# brick_serial_ble.net
KiCad netlist of a schematic drawn in EAGLE
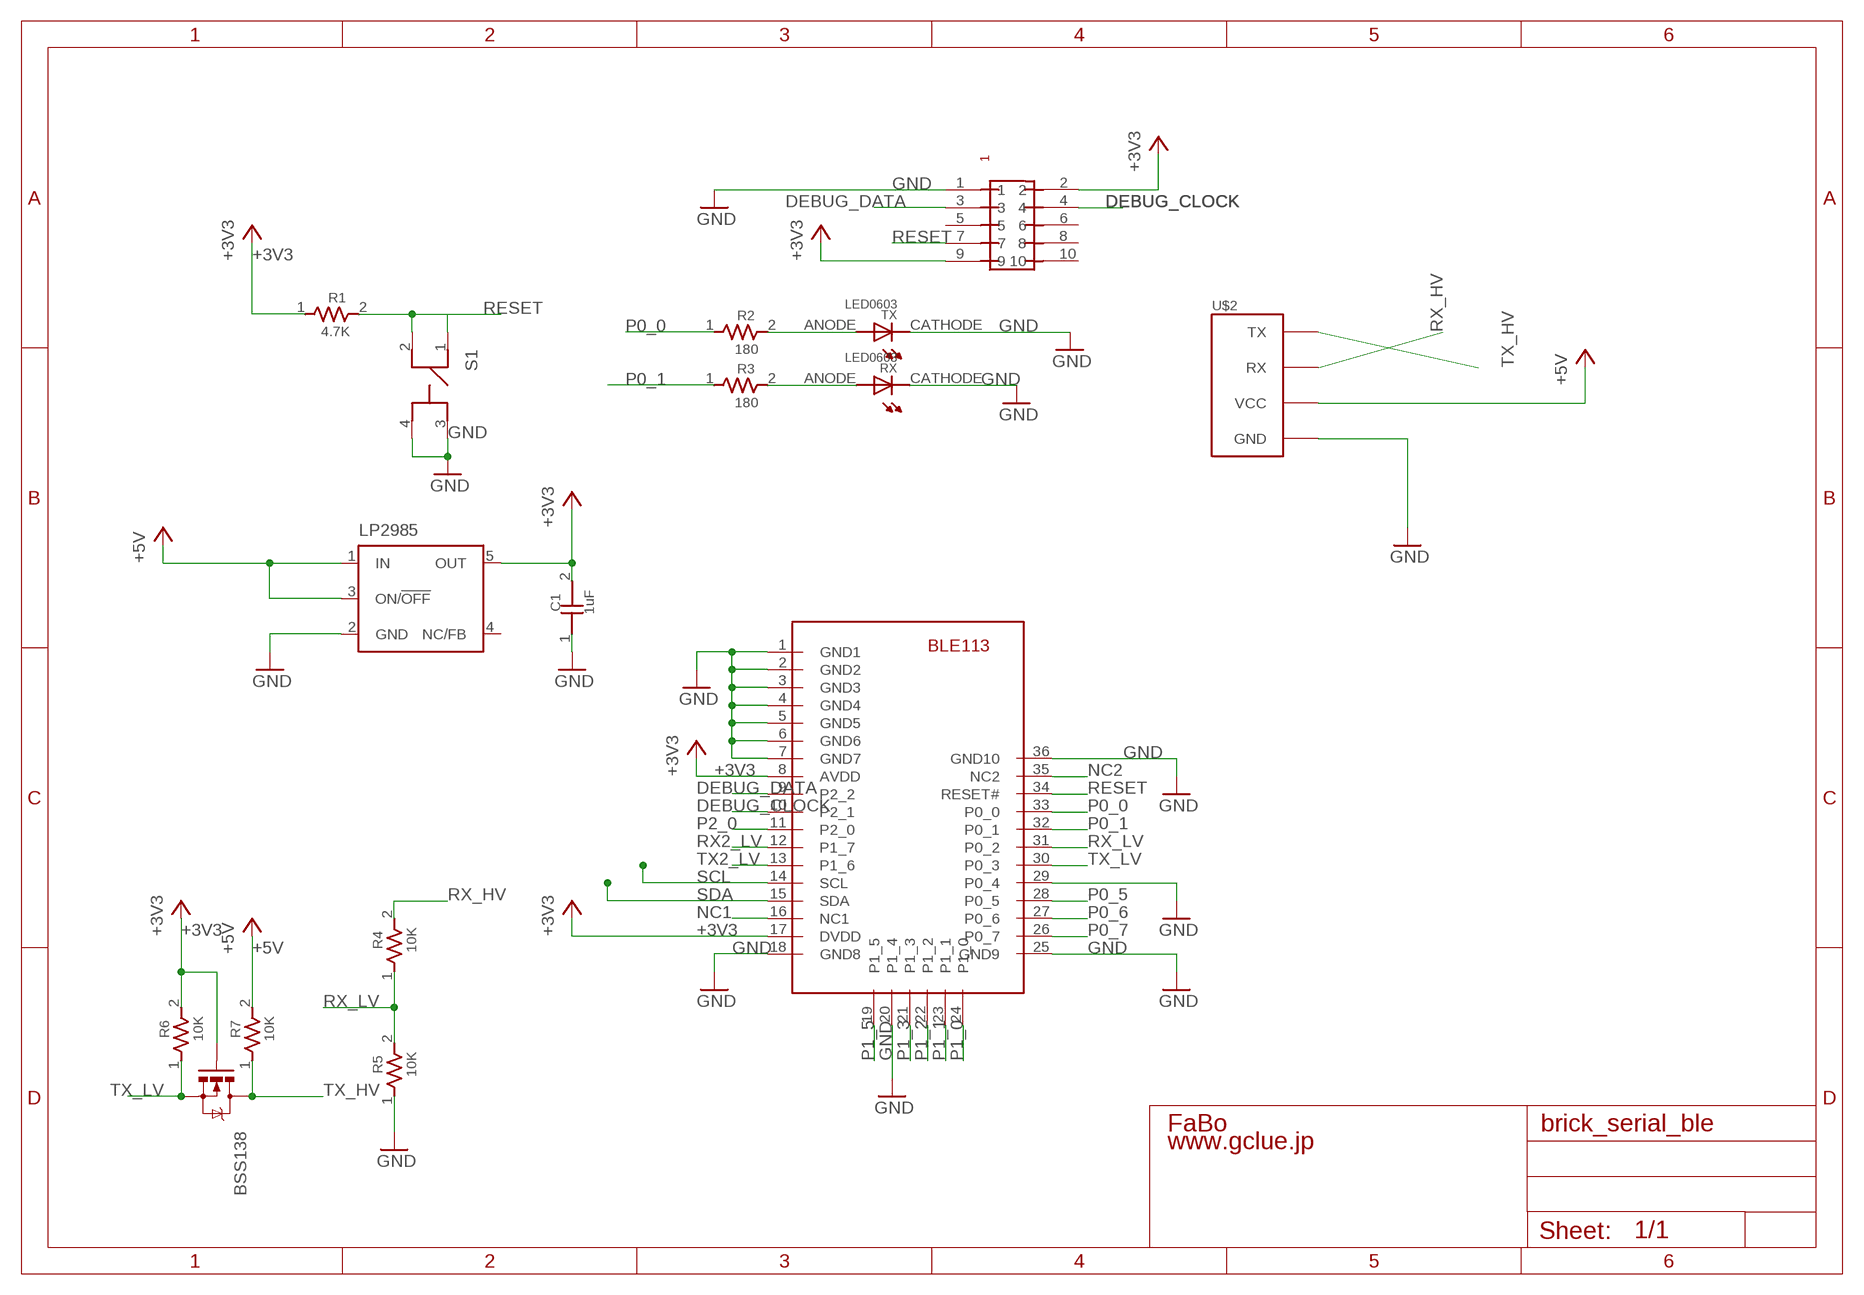
[diagram p0: schematic, sheet 1]

(export (version "E")
  (design (tool "Eeschema 10.0.6"))
  (components
    (comp (ref "BSS138")
      (value "MOSFET-NCHANNELSMD")
      (footprint "eagle-import:SOT23-3")
      (libsource (lib "eagle-import") (part "MOSFET-NCHANNELSMD"))
    )
    (comp (ref "C1")
      (value "1uF")
      (footprint "eagle-import:0603")
      (libsource (lib "eagle-import") (part "CAPACITOR0603"))
    )
    (comp (ref "LP2985")
      (value "LP2985-XXDBVR33")
      (footprint "eagle-import:SOT23-DBV")
      (libsource (lib "eagle-import") (part "LP2985-XXDBVR33"))
    )
    (comp (ref "R1")
      (value "4.7K")
      (footprint "eagle-import:0603")
      (libsource (lib "eagle-import") (part "RESISTOR0603"))
    )
    (comp (ref "R2")
      (value "180")
      (footprint "eagle-import:0603")
      (libsource (lib "eagle-import") (part "RESISTOR0603"))
    )
    (comp (ref "R3")
      (value "180")
      (footprint "eagle-import:0603")
      (libsource (lib "eagle-import") (part "RESISTOR0603"))
    )
    (comp (ref "R4")
      (value "10K")
      (footprint "eagle-import:0603")
      (libsource (lib "eagle-import") (part "RESISTOR0603"))
    )
    (comp (ref "R5")
      (value "10K")
      (footprint "eagle-import:0603")
      (libsource (lib "eagle-import") (part "RESISTOR0603"))
    )
    (comp (ref "R6")
      (value "10K")
      (footprint "eagle-import:0603")
      (libsource (lib "eagle-import") (part "RESISTOR0603"))
    )
    (comp (ref "R7")
      (value "10K")
      (footprint "eagle-import:0603")
      (libsource (lib "eagle-import") (part "RESISTOR0603"))
    )
    (comp (ref "RX")
      (value "LED0603")
      (footprint "eagle-import:0603")
      (libsource (lib "eagle-import") (part "LED0603"))
    )
    (comp (ref "S1")
      (value "SWITCH-LS6J2M-T")
      (footprint "eagle-import:SWITCH-LS6J2M-T")
      (libsource (lib "eagle-import") (part "SWITCH-LS6J2M-T"))
    )
    (comp (ref "TX")
      (value "LED0603")
      (footprint "eagle-import:0603")
      (libsource (lib "eagle-import") (part "LED0603"))
    )
    (comp (ref "U$1")
      (value "PIN-HEADER-SMT(1.27MM)2X5")
      (footprint "eagle-import:PIN-HEADER-SMT(1.27MM)2X5")
      (libsource (lib "eagle-import") (part "PIN-HEADER-SMT(1.27MM)2X5"))
    )
    (comp (ref "U$2")
      (value "BRICK_SERIAL")
      (footprint "eagle-import:BRICK_SERIAL")
      (libsource (lib "eagle-import") (part "BRICK_SERIAL"))
    )
    (comp (ref "U$6")
      (value "BLUEGIGA-BLE113")
      (footprint "eagle-import:BLUEGIGA-BLE113")
      (libsource (lib "eagle-import") (part "BLUEGIGA-BLE113"))
    )
  )
  (nets
    (net (code "1") (name "+3V3") (class "Default")
      (node (ref "BSS138") (pin "1") (pinfunction "G_1") (pintype "passive"))
      (node (ref "C1") (pin "2") (pinfunction "2_2") (pintype "passive"))
      (node (ref "LP2985") (pin "5") (pinfunction "OUT_5") (pintype "passive"))
      (node (ref "R1") (pin "1") (pinfunction "1_1") (pintype "passive"))
      (node (ref "R6") (pin "2") (pinfunction "2_2") (pintype "passive"))
      (node (ref "U$1") (pin "2") (pinfunction "2_2") (pintype "bidirectional"))
      (node (ref "U$1") (pin "9") (pinfunction "9_9") (pintype "bidirectional"))
      (node (ref "U$6") (pin "17") (pinfunction "DVDD_17") (pintype "bidirectional"))
      (node (ref "U$6") (pin "8") (pinfunction "AVDD_8") (pintype "bidirectional"))
    )
    (net (code "2") (name "+5V") (class "Default")
      (node (ref "LP2985") (pin "1") (pinfunction "IN_1") (pintype "input"))
      (node (ref "LP2985") (pin "3") (pinfunction "ON/~{OFF}_3") (pintype "input"))
      (node (ref "R7") (pin "2") (pinfunction "2_2") (pintype "passive"))
      (node (ref "U$2") (pin "VCC") (pinfunction "VCC_VCC") (pintype "bidirectional"))
    )
    (net (code "3") (name "/DEBUG_CLOCK") (class "Default")
      (node (ref "U$1") (pin "4") (pinfunction "4_4") (pintype "bidirectional"))
      (node (ref "U$6") (pin "10") (pinfunction "P2_1_10") (pintype "bidirectional"))
    )
    (net (code "4") (name "/DEBUG_DATA") (class "Default")
      (node (ref "U$1") (pin "3") (pinfunction "3_3") (pintype "bidirectional"))
      (node (ref "U$6") (pin "9") (pinfunction "P2_2_9") (pintype "bidirectional"))
    )
    (net (code "5") (name "/NC1") (class "Default")
      (node (ref "U$6") (pin "16") (pinfunction "NC1_16") (pintype "bidirectional"))
    )
    (net (code "6") (name "/NC2") (class "Default")
      (node (ref "U$6") (pin "35") (pinfunction "NC2_35") (pintype "bidirectional"))
    )
    (net (code "7") (name "/P0_0") (class "Default")
      (node (ref "R2") (pin "1") (pinfunction "1_1") (pintype "passive"))
      (node (ref "U$6") (pin "33") (pinfunction "P0_0_33") (pintype "bidirectional"))
    )
    (net (code "8") (name "/P0_1") (class "Default")
      (node (ref "R3") (pin "1") (pinfunction "1_1") (pintype "passive"))
      (node (ref "U$6") (pin "32") (pinfunction "P0_1_32") (pintype "bidirectional"))
    )
    (net (code "9") (name "/P0_5") (class "Default")
      (node (ref "U$6") (pin "28") (pinfunction "P0_5_28") (pintype "bidirectional"))
    )
    (net (code "10") (name "/P0_6") (class "Default")
      (node (ref "U$6") (pin "27") (pinfunction "P0_6_27") (pintype "bidirectional"))
    )
    (net (code "11") (name "/P0_7") (class "Default")
      (node (ref "U$6") (pin "26") (pinfunction "P0_7_26") (pintype "bidirectional"))
    )
    (net (code "12") (name "/P1_0") (class "Default")
      (node (ref "U$6") (pin "24") (pinfunction "P1_0_24") (pintype "bidirectional"))
    )
    (net (code "13") (name "/P1_1") (class "Default")
      (node (ref "U$6") (pin "23") (pinfunction "P1_1_23") (pintype "bidirectional"))
    )
    (net (code "14") (name "/P1_2") (class "Default")
      (node (ref "U$6") (pin "22") (pinfunction "P1_2_22") (pintype "bidirectional"))
    )
    (net (code "15") (name "/P1_3") (class "Default")
      (node (ref "U$6") (pin "21") (pinfunction "P1_3_21") (pintype "bidirectional"))
    )
    (net (code "16") (name "/P1_5") (class "Default")
      (node (ref "U$6") (pin "19") (pinfunction "P1_5_19") (pintype "bidirectional"))
    )
    (net (code "17") (name "/P2_0") (class "Default")
      (node (ref "U$6") (pin "11") (pinfunction "P2_0_11") (pintype "bidirectional"))
    )
    (net (code "18") (name "/RESET") (class "Default")
      (node (ref "R1") (pin "2") (pinfunction "2_2") (pintype "passive"))
      (node (ref "S1") (pin "1") (pinfunction "1_1") (pintype "bidirectional"))
      (node (ref "S1") (pin "2") (pinfunction "2_2") (pintype "bidirectional"))
      (node (ref "U$1") (pin "7") (pinfunction "7_7") (pintype "bidirectional"))
      (node (ref "U$6") (pin "34") (pinfunction "RESET#_34") (pintype "bidirectional"))
    )
    (net (code "19") (name "/RX2_LV") (class "Default")
      (node (ref "U$6") (pin "12") (pinfunction "P1_7_12") (pintype "bidirectional"))
    )
    (net (code "20") (name "/RX_HV") (class "Default")
      (node (ref "R4") (pin "2") (pinfunction "2_2") (pintype "passive"))
      (node (ref "U$2") (pin "RX") (pinfunction "RX_RX") (pintype "bidirectional"))
    )
    (net (code "21") (name "/RX_LV") (class "Default")
      (node (ref "R4") (pin "1") (pinfunction "1_1") (pintype "passive"))
      (node (ref "R5") (pin "2") (pinfunction "2_2") (pintype "passive"))
      (node (ref "U$6") (pin "31") (pinfunction "P0_2_31") (pintype "bidirectional"))
    )
    (net (code "22") (name "/SCL") (class "Default")
      (node (ref "U$6") (pin "14") (pinfunction "SCL_14") (pintype "bidirectional"))
    )
    (net (code "23") (name "/SDA") (class "Default")
      (node (ref "U$6") (pin "15") (pinfunction "SDA_15") (pintype "bidirectional"))
    )
    (net (code "24") (name "/TX2_LV") (class "Default")
      (node (ref "U$6") (pin "13") (pinfunction "P1_6_13") (pintype "bidirectional"))
    )
    (net (code "25") (name "/TX_HV") (class "Default")
      (node (ref "BSS138") (pin "3") (pinfunction "D_3") (pintype "passive"))
      (node (ref "R7") (pin "1") (pinfunction "1_1") (pintype "passive"))
      (node (ref "U$2") (pin "TX") (pinfunction "TX_TX") (pintype "bidirectional"))
    )
    (net (code "26") (name "/TX_LV") (class "Default")
      (node (ref "BSS138") (pin "2") (pinfunction "S_2") (pintype "passive"))
      (node (ref "R6") (pin "1") (pinfunction "1_1") (pintype "passive"))
      (node (ref "U$6") (pin "30") (pinfunction "P0_3_30") (pintype "bidirectional"))
    )
    (net (code "27") (name "GND") (class "Default")
      (node (ref "C1") (pin "1") (pinfunction "1_1") (pintype "passive"))
      (node (ref "LP2985") (pin "2") (pinfunction "GND_2") (pintype "power_in"))
      (node (ref "R5") (pin "1") (pinfunction "1_1") (pintype "passive"))
      (node (ref "RX") (pin "CATHODE") (pinfunction "CATHODE_CATHODE") (pintype "passive"))
      (node (ref "S1") (pin "3") (pinfunction "3_3") (pintype "bidirectional"))
      (node (ref "S1") (pin "4") (pinfunction "4_4") (pintype "bidirectional"))
      (node (ref "TX") (pin "CATHODE") (pinfunction "CATHODE_CATHODE") (pintype "passive"))
      (node (ref "U$1") (pin "1") (pinfunction "1_1") (pintype "bidirectional"))
      (node (ref "U$2") (pin "GND") (pinfunction "GND_GND") (pintype "bidirectional"))
      (node (ref "U$6") (pin "1") (pinfunction "GND1_1") (pintype "bidirectional"))
      (node (ref "U$6") (pin "18") (pinfunction "GND8_18") (pintype "bidirectional"))
      (node (ref "U$6") (pin "2") (pinfunction "GND2_2") (pintype "bidirectional"))
      (node (ref "U$6") (pin "20") (pinfunction "P1_4_20") (pintype "bidirectional"))
      (node (ref "U$6") (pin "25") (pinfunction "GND9_25") (pintype "bidirectional"))
      (node (ref "U$6") (pin "29") (pinfunction "P0_4_29") (pintype "bidirectional"))
      (node (ref "U$6") (pin "3") (pinfunction "GND3_3") (pintype "bidirectional"))
      (node (ref "U$6") (pin "36") (pinfunction "GND10_36") (pintype "bidirectional"))
      (node (ref "U$6") (pin "4") (pinfunction "GND4_4") (pintype "bidirectional"))
      (node (ref "U$6") (pin "5") (pinfunction "GND5_5") (pintype "bidirectional"))
      (node (ref "U$6") (pin "6") (pinfunction "GND6_6") (pintype "bidirectional"))
      (node (ref "U$6") (pin "7") (pinfunction "GND7_7") (pintype "bidirectional"))
    )
    (net (code "28") (name "Net-(R2-Pad2)") (class "Default")
      (node (ref "R2") (pin "2") (pinfunction "2_2") (pintype "passive"))
      (node (ref "TX") (pin "ANODE") (pinfunction "ANODE_ANODE") (pintype "passive"))
    )
    (net (code "29") (name "Net-(R3-Pad2)") (class "Default")
      (node (ref "R3") (pin "2") (pinfunction "2_2") (pintype "passive"))
      (node (ref "RX") (pin "ANODE") (pinfunction "ANODE_ANODE") (pintype "passive"))
    )
    (net (code "30") (name "unconnected-(LP2985-NC{slash}FB-Pad4)") (class "Default")
      (node (ref "LP2985") (pin "4") (pinfunction "NC/FB_4") (pintype "passive"))
    )
    (net (code "31") (name "unconnected-(U$1-Pad5)") (class "Default")
      (node (ref "U$1") (pin "5") (pinfunction "5_5") (pintype "bidirectional"))
    )
    (net (code "32") (name "unconnected-(U$1-Pad6)") (class "Default")
      (node (ref "U$1") (pin "6") (pinfunction "6_6") (pintype "bidirectional"))
    )
    (net (code "33") (name "unconnected-(U$1-Pad8)") (class "Default")
      (node (ref "U$1") (pin "8") (pinfunction "8_8") (pintype "bidirectional"))
    )
    (net (code "34") (name "unconnected-(U$1-Pad10)") (class "Default")
      (node (ref "U$1") (pin "10") (pinfunction "10_10") (pintype "bidirectional"))
    )
  )
)
